# ArduSensor-Flex.net
KiCad netlist of a schematic drawn in EAGLE
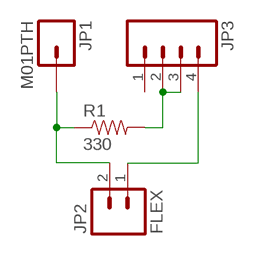
[diagram p0: schematic, sheet 1]

(export (version "E")
  (design (tool "Eeschema 10.0.6"))
  (components
    (comp (ref "JP1")
      (value "M01PTH")
      (footprint "eagle-import:1X01")
      (libsource (lib "eagle-import") (part "M01PTH"))
    )
    (comp (ref "JP2")
      (value "FLEX")
      (footprint "eagle-import:1X02")
      (libsource (lib "eagle-import") (part "M02PTH"))
    )
    (comp (ref "JP3")
      (value "M04PTH")
      (footprint "eagle-import:1X04")
      (libsource (lib "eagle-import") (part "M04PTH"))
    )
    (comp (ref "R1")
      (value "330")
      (footprint "eagle-import:AXIAL-0.3")
      (libsource (lib "eagle-import") (part "RESISTORAXIAL-0.3"))
    )
  )
  (nets
    (net (code "1") (name "Net-(JP2-Pad1)") (class "Default")
      (node (ref "JP2") (pin "1") (pinfunction "1_1") (pintype "passive"))
      (node (ref "JP3") (pin "4") (pinfunction "4_4") (pintype "passive"))
    )
    (net (code "2") (name "Net-(R1-1)") (class "Default")
      (node (ref "JP1") (pin "1") (pinfunction "1_1") (pintype "passive"))
      (node (ref "JP2") (pin "2") (pinfunction "2_2") (pintype "passive"))
      (node (ref "R1") (pin "P$1") (pinfunction "1_P$1") (pintype "passive"))
    )
    (net (code "3") (name "Net-(R1-2)") (class "Default")
      (node (ref "JP3") (pin "2") (pinfunction "2_2") (pintype "passive"))
      (node (ref "JP3") (pin "3") (pinfunction "3_3") (pintype "passive"))
      (node (ref "R1") (pin "P$2") (pinfunction "2_P$2") (pintype "passive"))
    )
    (net (code "4") (name "unconnected-(JP3-Pad1)") (class "Default")
      (node (ref "JP3") (pin "1") (pinfunction "1_1") (pintype "passive"))
    )
  )
)
